# design.net
KiCad netlist of a schematic drawn in EasyEDA Pro
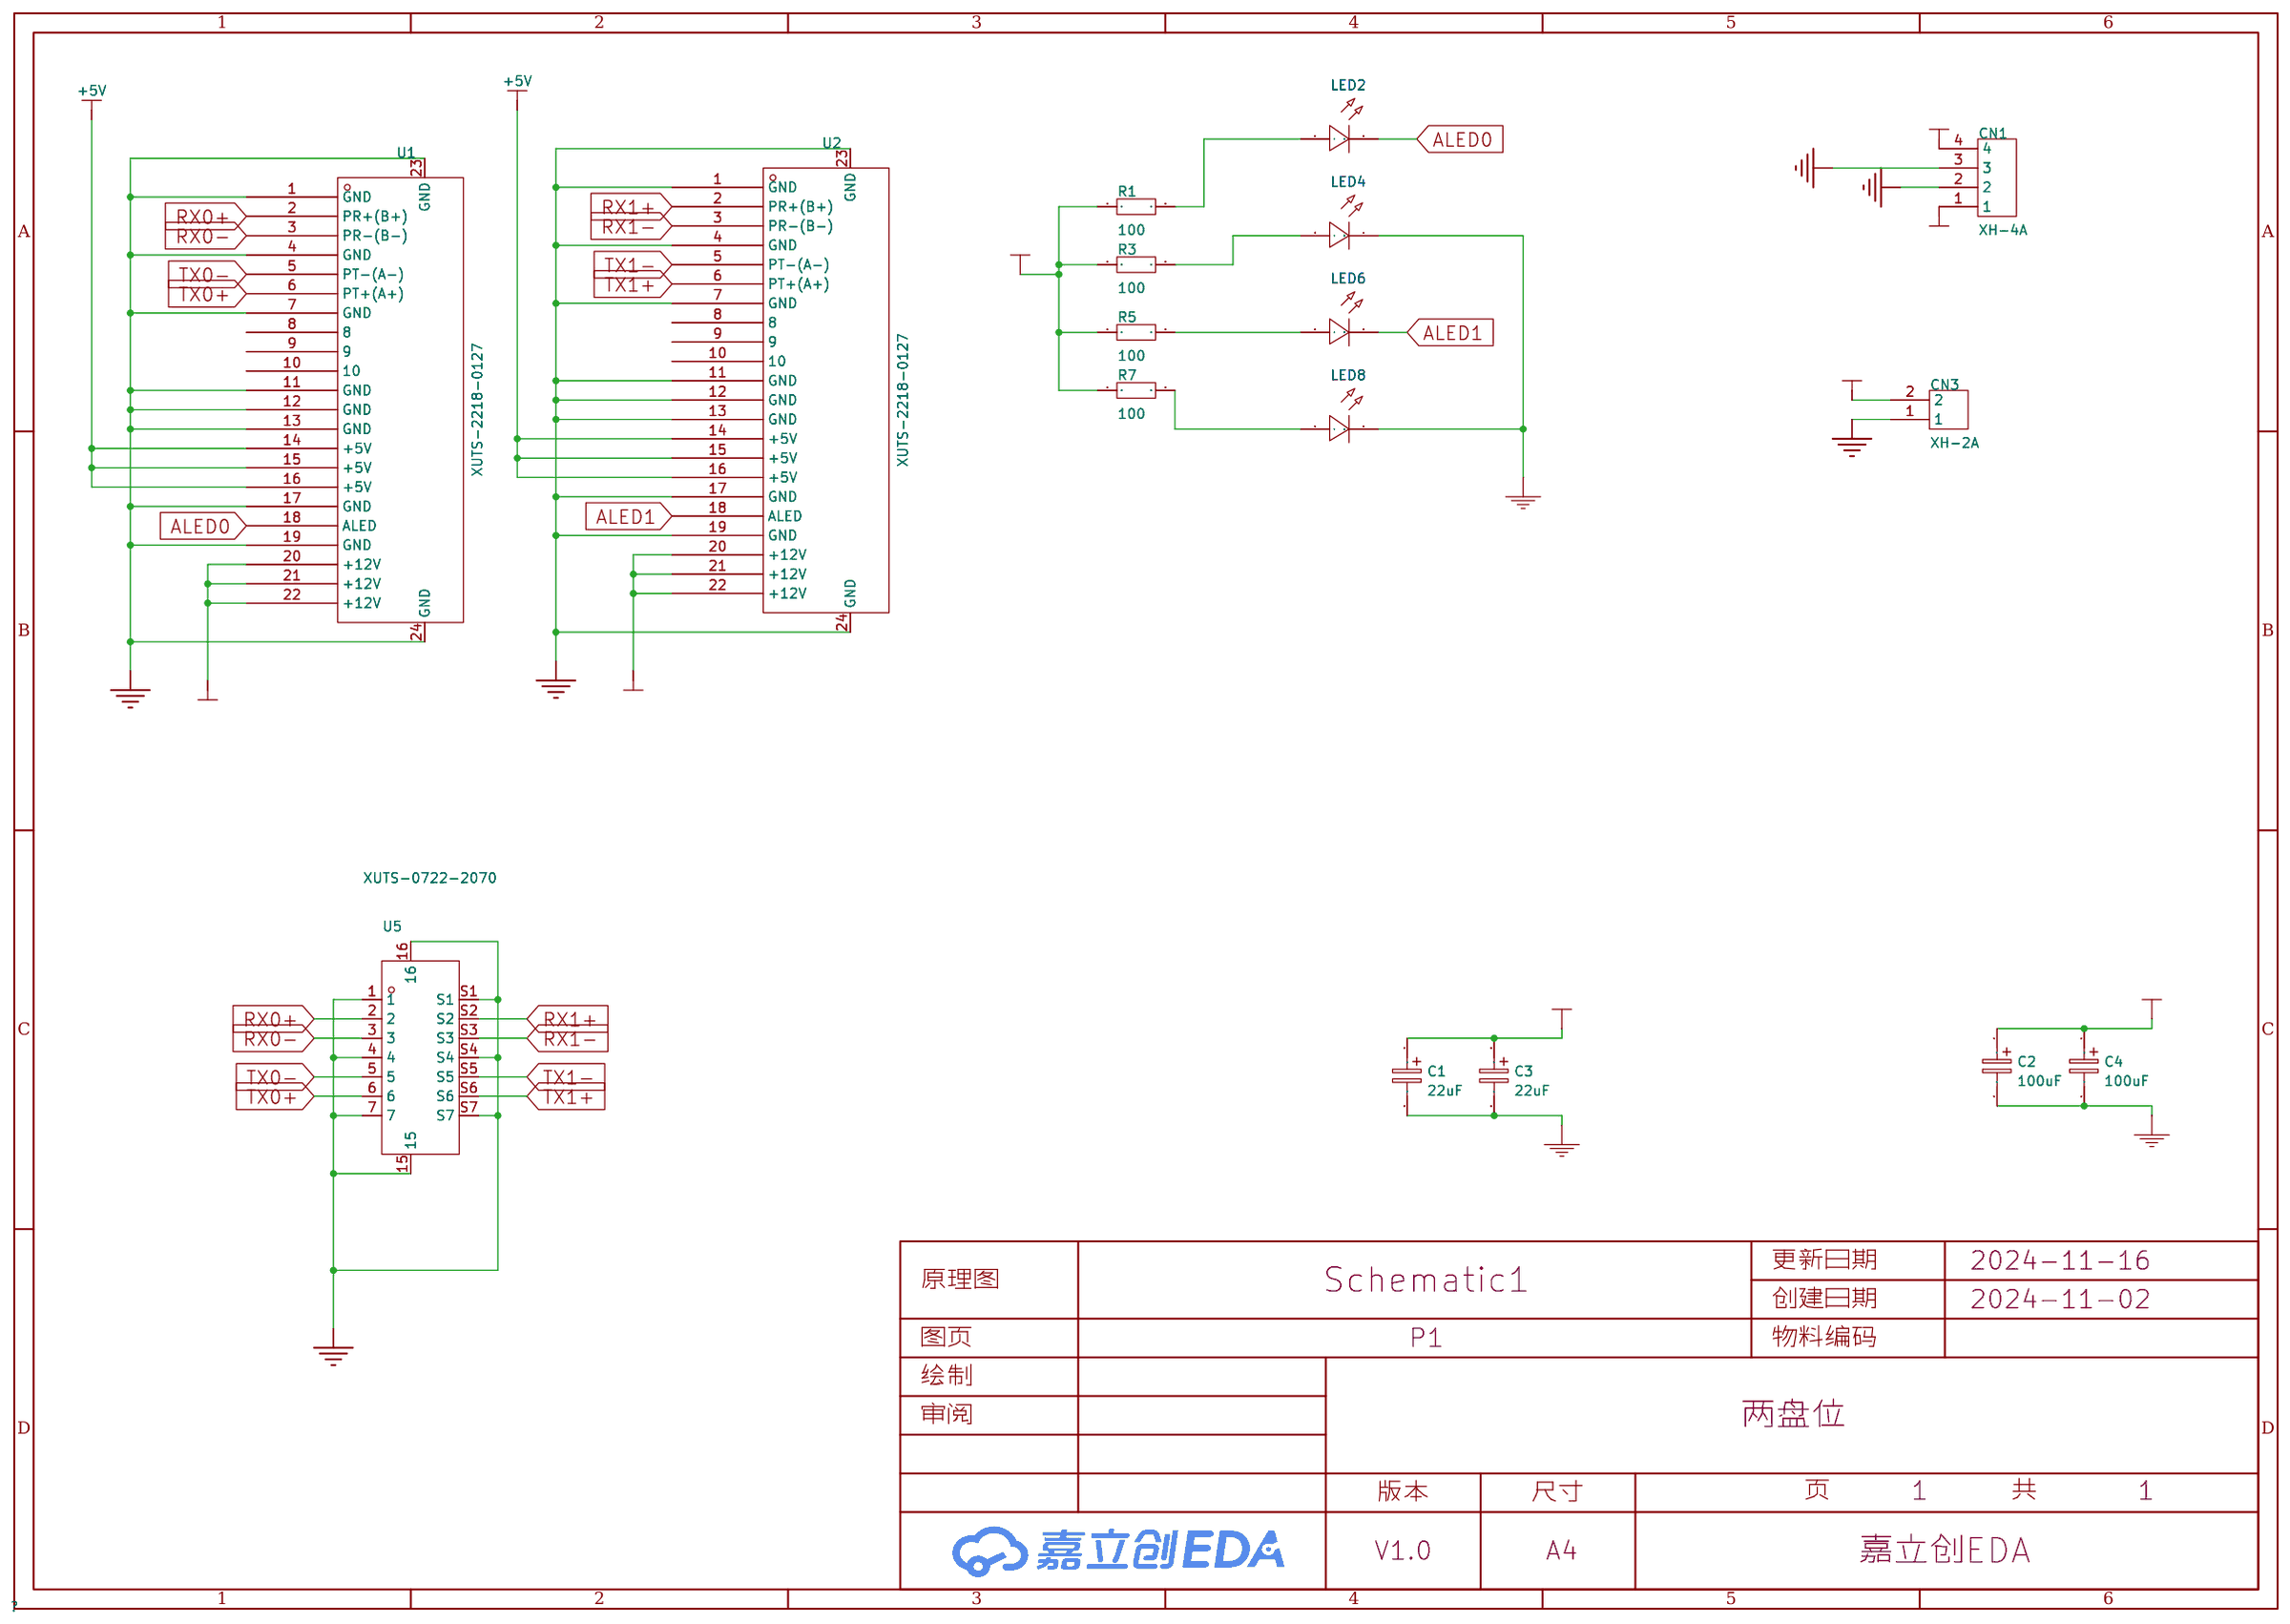
[diagram p0: schematic sheet]

(export (version "E")
  (design (tool "Eeschema 10.0.6"))
  (components
    (comp (ref "C1")
      (value "22uF")
      (footprint "easyedapro:CAP-SMD_L7.3-W4.3-R-RD")
      (description "容值:22uF;精度:±20%;额定电压:20V;等效串联电阻:800mΩ@100kHz;")
      (fields (field (name "Manufacturer Part") "T491D226M020AT") (field (name "Manufacturer") "KEMET(基美)"))
      (libsource (lib "easyedapro") (part "T491D226M020AT"))
    )
    (comp (ref "C2")
      (value "100uF")
      (footprint "easyedapro:CAP-SMD_L7.3-W4.3-R-RD")
      (description "容值:22uF;精度:±20%;额定电压:20V;等效串联电阻:800mΩ@100kHz;")
      (fields (field (name "Manufacturer Part") "T491D226M020AT") (field (name "Manufacturer") "KEMET(基美)"))
      (libsource (lib "easyedapro") (part "T491D226M020AT"))
    )
    (comp (ref "C3")
      (value "22uF")
      (footprint "easyedapro:CAP-SMD_L7.3-W4.3-R-RD")
      (description "容值:22uF;精度:±20%;额定电压:20V;等效串联电阻:800mΩ@100kHz;")
      (fields (field (name "Manufacturer Part") "T491D226M020AT") (field (name "Manufacturer") "KEMET(基美)"))
      (libsource (lib "easyedapro") (part "T491D226M020AT"))
    )
    (comp (ref "C4")
      (value "100uF")
      (footprint "easyedapro:CAP-SMD_L7.3-W4.3-R-RD")
      (description "容值:22uF;精度:±20%;额定电压:20V;等效串联电阻:800mΩ@100kHz;")
      (fields (field (name "Manufacturer Part") "T491D226M020AT") (field (name "Manufacturer") "KEMET(基美)"))
      (libsource (lib "easyedapro") (part "T491D226M020AT"))
    )
    (comp (ref "CN1")
      (value "XH-4A")
      (footprint "easyedapro:CONN-TH_4P-P2.50_XH-4A")
      (description "插针结构:1x4P;间距:2.5mm;安装方式:-;参考系列:XH;总PIN数:4P;排数:1;每排PIN数:4;行距:-;触头材质:磷青铜;")
      (fields (field (name "Manufacturer") "BOOMELE(博穆精密)"))
      (libsource (lib "easyedapro") (part "XH-4A"))
    )
    (comp (ref "CN3")
      (value "XH-2A")
      (footprint "easyedapro:CONN-TH_XH-2A")
      (description "插针结构:1x2P;间距:2.5mm;安装方式:-;参考系列:XH;总PIN数:2P;排数:1;每排PIN数:2;行距:-;触头材质:-;")
      (fields (field (name "Manufacturer") "BOOMELE(博穆精密)"))
      (libsource (lib "easyedapro") (part "XH-2A"))
    )
    (comp (ref "LED2")
      (value "~")
      (footprint "easyedapro:LED_0805")
      (libsource (lib "easyedapro") (part "LED_B"))
    )
    (comp (ref "LED4")
      (value "~")
      (footprint "easyedapro:LED_0805")
      (libsource (lib "easyedapro") (part "LED_G"))
    )
    (comp (ref "LED6")
      (value "~")
      (footprint "easyedapro:LED_0805")
      (libsource (lib "easyedapro") (part "LED_B"))
    )
    (comp (ref "LED8")
      (value "~")
      (footprint "easyedapro:LED_0805")
      (libsource (lib "easyedapro") (part "LED_G"))
    )
    (comp (ref "R1") (value "100") (footprint "easyedapro:R0805") (libsource (lib "easyedapro") (part "电阻")))
    (comp (ref "R3") (value "100") (footprint "easyedapro:R0805") (libsource (lib "easyedapro") (part "电阻")))
    (comp (ref "R5") (value "100") (footprint "easyedapro:R0805") (libsource (lib "easyedapro") (part "电阻")))
    (comp (ref "R7") (value "100") (footprint "easyedapro:R0805") (libsource (lib "easyedapro") (part "电阻")))
    (comp (ref "U1")
      (value "XUTS-2218-0127")
      (footprint "easyedapro:SATA")
      (description "连接器类型:SATA;间距:1.27mm;引脚总数:22P;安装方式:立贴;工作温度范围:-40°C~+105°C;")
      (fields (field (name "Manufacturer") "LX(连欣科技)"))
      (libsource (lib "easyedapro") (part "XUTS-2218-0127"))
    )
    (comp (ref "U2")
      (value "XUTS-2218-0127")
      (footprint "easyedapro:SATA")
      (description "连接器类型:SATA;间距:1.27mm;引脚总数:22P;安装方式:立贴;工作温度范围:-40°C~+105°C;")
      (fields (field (name "Manufacturer") "LX(连欣科技)"))
      (libsource (lib "easyedapro") (part "XUTS-2218-0127"))
    )
    (comp (ref "U5")
      (value "XUTS-0722-2070")
      (footprint "easyedapro:CONN-TH_XUTS-0722-2070")
      (description "双层SATA 7PIN卧式插板式  SATA连接器")
      (fields (field (name "Manufacturer") "LX(连欣科技)"))
      (libsource (lib "easyedapro") (part "XUTS-0722-2070"))
    )
  )
  (nets
    (net (code "1") (name "+5V") (class "Default")
      (node (ref "C1") (pin "1") (pinfunction "1_1") (pintype "input"))
      (node (ref "C3") (pin "1") (pinfunction "1_1") (pintype "input"))
      (node (ref "CN1") (pin "1") (pinfunction "1_1") (pintype "unspecified"))
      (node (ref "R1") (pin "1") (pinfunction "1_1") (pintype "input"))
      (node (ref "R3") (pin "1") (pinfunction "1_1") (pintype "input"))
      (node (ref "R5") (pin "1") (pinfunction "1_1") (pintype "input"))
      (node (ref "R7") (pin "1") (pinfunction "1_1") (pintype "input"))
      (node (ref "U1") (pin "14") (pinfunction "+5V_14") (pintype "unspecified"))
      (node (ref "U1") (pin "15") (pinfunction "+5V_15") (pintype "unspecified"))
      (node (ref "U1") (pin "16") (pinfunction "+5V_16") (pintype "unspecified"))
      (node (ref "U2") (pin "14") (pinfunction "+5V_14") (pintype "unspecified"))
      (node (ref "U2") (pin "15") (pinfunction "+5V_15") (pintype "unspecified"))
      (node (ref "U2") (pin "16") (pinfunction "+5V_16") (pintype "unspecified"))
    )
    (net (code "2") (name "+12V") (class "Default")
      (node (ref "C2") (pin "1") (pinfunction "1_1") (pintype "input"))
      (node (ref "C4") (pin "1") (pinfunction "1_1") (pintype "input"))
      (node (ref "CN1") (pin "4") (pinfunction "4_4") (pintype "unspecified"))
      (node (ref "CN3") (pin "2") (pinfunction "2_2") (pintype "unspecified"))
      (node (ref "U1") (pin "20") (pinfunction "+12V_20") (pintype "unspecified"))
      (node (ref "U1") (pin "21") (pinfunction "+12V_21") (pintype "unspecified"))
      (node (ref "U1") (pin "22") (pinfunction "+12V_22") (pintype "unspecified"))
      (node (ref "U2") (pin "20") (pinfunction "+12V_20") (pintype "unspecified"))
      (node (ref "U2") (pin "21") (pinfunction "+12V_21") (pintype "unspecified"))
      (node (ref "U2") (pin "22") (pinfunction "+12V_22") (pintype "unspecified"))
    )
    (net (code "3") (name "ALED0") (class "Default")
      (node (ref "LED2") (pin "1") (pinfunction "C_1") (pintype "input"))
      (node (ref "U1") (pin "18") (pinfunction "ALED_18") (pintype "unspecified"))
    )
    (net (code "4") (name "ALED1") (class "Default")
      (node (ref "LED6") (pin "1") (pinfunction "C_1") (pintype "input"))
      (node (ref "U2") (pin "18") (pinfunction "ALED_18") (pintype "unspecified"))
    )
    (net (code "5") (name "GND") (class "Default")
      (node (ref "C1") (pin "2") (pinfunction "2_2") (pintype "input"))
      (node (ref "C2") (pin "2") (pinfunction "2_2") (pintype "input"))
      (node (ref "C3") (pin "2") (pinfunction "2_2") (pintype "input"))
      (node (ref "C4") (pin "2") (pinfunction "2_2") (pintype "input"))
      (node (ref "CN1") (pin "2") (pinfunction "2_2") (pintype "unspecified"))
      (node (ref "CN1") (pin "3") (pinfunction "3_3") (pintype "unspecified"))
      (node (ref "CN3") (pin "1") (pinfunction "1_1") (pintype "unspecified"))
      (node (ref "LED4") (pin "1") (pinfunction "C_1") (pintype "input"))
      (node (ref "LED8") (pin "1") (pinfunction "C_1") (pintype "input"))
      (node (ref "U1") (pin "1") (pinfunction "GND_1") (pintype "unspecified"))
      (node (ref "U1") (pin "11") (pinfunction "GND_11") (pintype "unspecified"))
      (node (ref "U1") (pin "12") (pinfunction "GND_12") (pintype "unspecified"))
      (node (ref "U1") (pin "13") (pinfunction "GND_13") (pintype "unspecified"))
      (node (ref "U1") (pin "17") (pinfunction "GND_17") (pintype "unspecified"))
      (node (ref "U1") (pin "19") (pinfunction "GND_19") (pintype "unspecified"))
      (node (ref "U1") (pin "23") (pinfunction "GND_23") (pintype "unspecified"))
      (node (ref "U1") (pin "24") (pinfunction "GND_24") (pintype "unspecified"))
      (node (ref "U1") (pin "4") (pinfunction "GND_4") (pintype "unspecified"))
      (node (ref "U1") (pin "7") (pinfunction "GND_7") (pintype "unspecified"))
      (node (ref "U2") (pin "1") (pinfunction "GND_1") (pintype "unspecified"))
      (node (ref "U2") (pin "11") (pinfunction "GND_11") (pintype "unspecified"))
      (node (ref "U2") (pin "12") (pinfunction "GND_12") (pintype "unspecified"))
      (node (ref "U2") (pin "13") (pinfunction "GND_13") (pintype "unspecified"))
      (node (ref "U2") (pin "17") (pinfunction "GND_17") (pintype "unspecified"))
      (node (ref "U2") (pin "19") (pinfunction "GND_19") (pintype "unspecified"))
      (node (ref "U2") (pin "23") (pinfunction "GND_23") (pintype "unspecified"))
      (node (ref "U2") (pin "24") (pinfunction "GND_24") (pintype "unspecified"))
      (node (ref "U2") (pin "4") (pinfunction "GND_4") (pintype "unspecified"))
      (node (ref "U2") (pin "7") (pinfunction "GND_7") (pintype "unspecified"))
      (node (ref "U5") (pin "1") (pinfunction "1_1") (pintype "unspecified"))
      (node (ref "U5") (pin "15") (pinfunction "15_15") (pintype "unspecified"))
      (node (ref "U5") (pin "16") (pinfunction "16_16") (pintype "unspecified"))
      (node (ref "U5") (pin "4") (pinfunction "4_4") (pintype "unspecified"))
      (node (ref "U5") (pin "7") (pinfunction "7_7") (pintype "unspecified"))
      (node (ref "U5") (pin "S1") (pinfunction "S1_S1") (pintype "unspecified"))
      (node (ref "U5") (pin "S4") (pinfunction "S4_S4") (pintype "unspecified"))
      (node (ref "U5") (pin "S7") (pinfunction "S7_S7") (pintype "unspecified"))
    )
    (net (code "6") (name "Net-(LED2-A)") (class "Default")
      (node (ref "LED2") (pin "2") (pinfunction "A_2") (pintype "input"))
      (node (ref "R1") (pin "2") (pinfunction "2_2") (pintype "input"))
    )
    (net (code "7") (name "Net-(LED4-A)") (class "Default")
      (node (ref "LED4") (pin "2") (pinfunction "A_2") (pintype "input"))
      (node (ref "R3") (pin "2") (pinfunction "2_2") (pintype "input"))
    )
    (net (code "8") (name "Net-(LED6-A)") (class "Default")
      (node (ref "LED6") (pin "2") (pinfunction "A_2") (pintype "input"))
      (node (ref "R5") (pin "2") (pinfunction "2_2") (pintype "input"))
    )
    (net (code "9") (name "Net-(LED8-A)") (class "Default")
      (node (ref "LED8") (pin "2") (pinfunction "A_2") (pintype "input"))
      (node (ref "R7") (pin "2") (pinfunction "2_2") (pintype "input"))
    )
    (net (code "10") (name "RX0+") (class "Default")
      (node (ref "U1") (pin "2") (pinfunction "PR+(B+)_2") (pintype "unspecified"))
      (node (ref "U5") (pin "2") (pinfunction "2_2") (pintype "unspecified"))
    )
    (net (code "11") (name "RX0-") (class "Default")
      (node (ref "U1") (pin "3") (pinfunction "PR-(B-)_3") (pintype "unspecified"))
      (node (ref "U5") (pin "3") (pinfunction "3_3") (pintype "unspecified"))
    )
    (net (code "12") (name "RX1+") (class "Default")
      (node (ref "U2") (pin "2") (pinfunction "PR+(B+)_2") (pintype "unspecified"))
      (node (ref "U5") (pin "S2") (pinfunction "S2_S2") (pintype "unspecified"))
    )
    (net (code "13") (name "RX1-") (class "Default")
      (node (ref "U2") (pin "3") (pinfunction "PR-(B-)_3") (pintype "unspecified"))
      (node (ref "U5") (pin "S3") (pinfunction "S3_S3") (pintype "unspecified"))
    )
    (net (code "14") (name "TX0+") (class "Default")
      (node (ref "U1") (pin "6") (pinfunction "PT+(A+)_6") (pintype "unspecified"))
      (node (ref "U5") (pin "6") (pinfunction "6_6") (pintype "unspecified"))
    )
    (net (code "15") (name "TX0-") (class "Default")
      (node (ref "U1") (pin "5") (pinfunction "PT-(A-)_5") (pintype "unspecified"))
      (node (ref "U5") (pin "5") (pinfunction "5_5") (pintype "unspecified"))
    )
    (net (code "16") (name "TX1+") (class "Default")
      (node (ref "U2") (pin "6") (pinfunction "PT+(A+)_6") (pintype "unspecified"))
      (node (ref "U5") (pin "S6") (pinfunction "S6_S6") (pintype "unspecified"))
    )
    (net (code "17") (name "TX1-") (class "Default")
      (node (ref "U2") (pin "5") (pinfunction "PT-(A-)_5") (pintype "unspecified"))
      (node (ref "U5") (pin "S5") (pinfunction "S5_S5") (pintype "unspecified"))
    )
    (net (code "18") (name "unconnected-(U1-Pad8)") (class "Default")
      (node (ref "U1") (pin "8") (pinfunction "8_8") (pintype "unspecified"))
    )
    (net (code "19") (name "unconnected-(U1-Pad9)") (class "Default")
      (node (ref "U1") (pin "9") (pinfunction "9_9") (pintype "unspecified"))
    )
    (net (code "20") (name "unconnected-(U1-Pad10)") (class "Default")
      (node (ref "U1") (pin "10") (pinfunction "10_10") (pintype "unspecified"))
    )
    (net (code "21") (name "unconnected-(U2-Pad8)") (class "Default")
      (node (ref "U2") (pin "8") (pinfunction "8_8") (pintype "unspecified"))
    )
    (net (code "22") (name "unconnected-(U2-Pad9)") (class "Default")
      (node (ref "U2") (pin "9") (pinfunction "9_9") (pintype "unspecified"))
    )
    (net (code "23") (name "unconnected-(U2-Pad10)") (class "Default")
      (node (ref "U2") (pin "10") (pinfunction "10_10") (pintype "unspecified"))
    )
  )
)
